# kitchen-timer.net
KiCad netlist of a schematic drawn in EAGLE
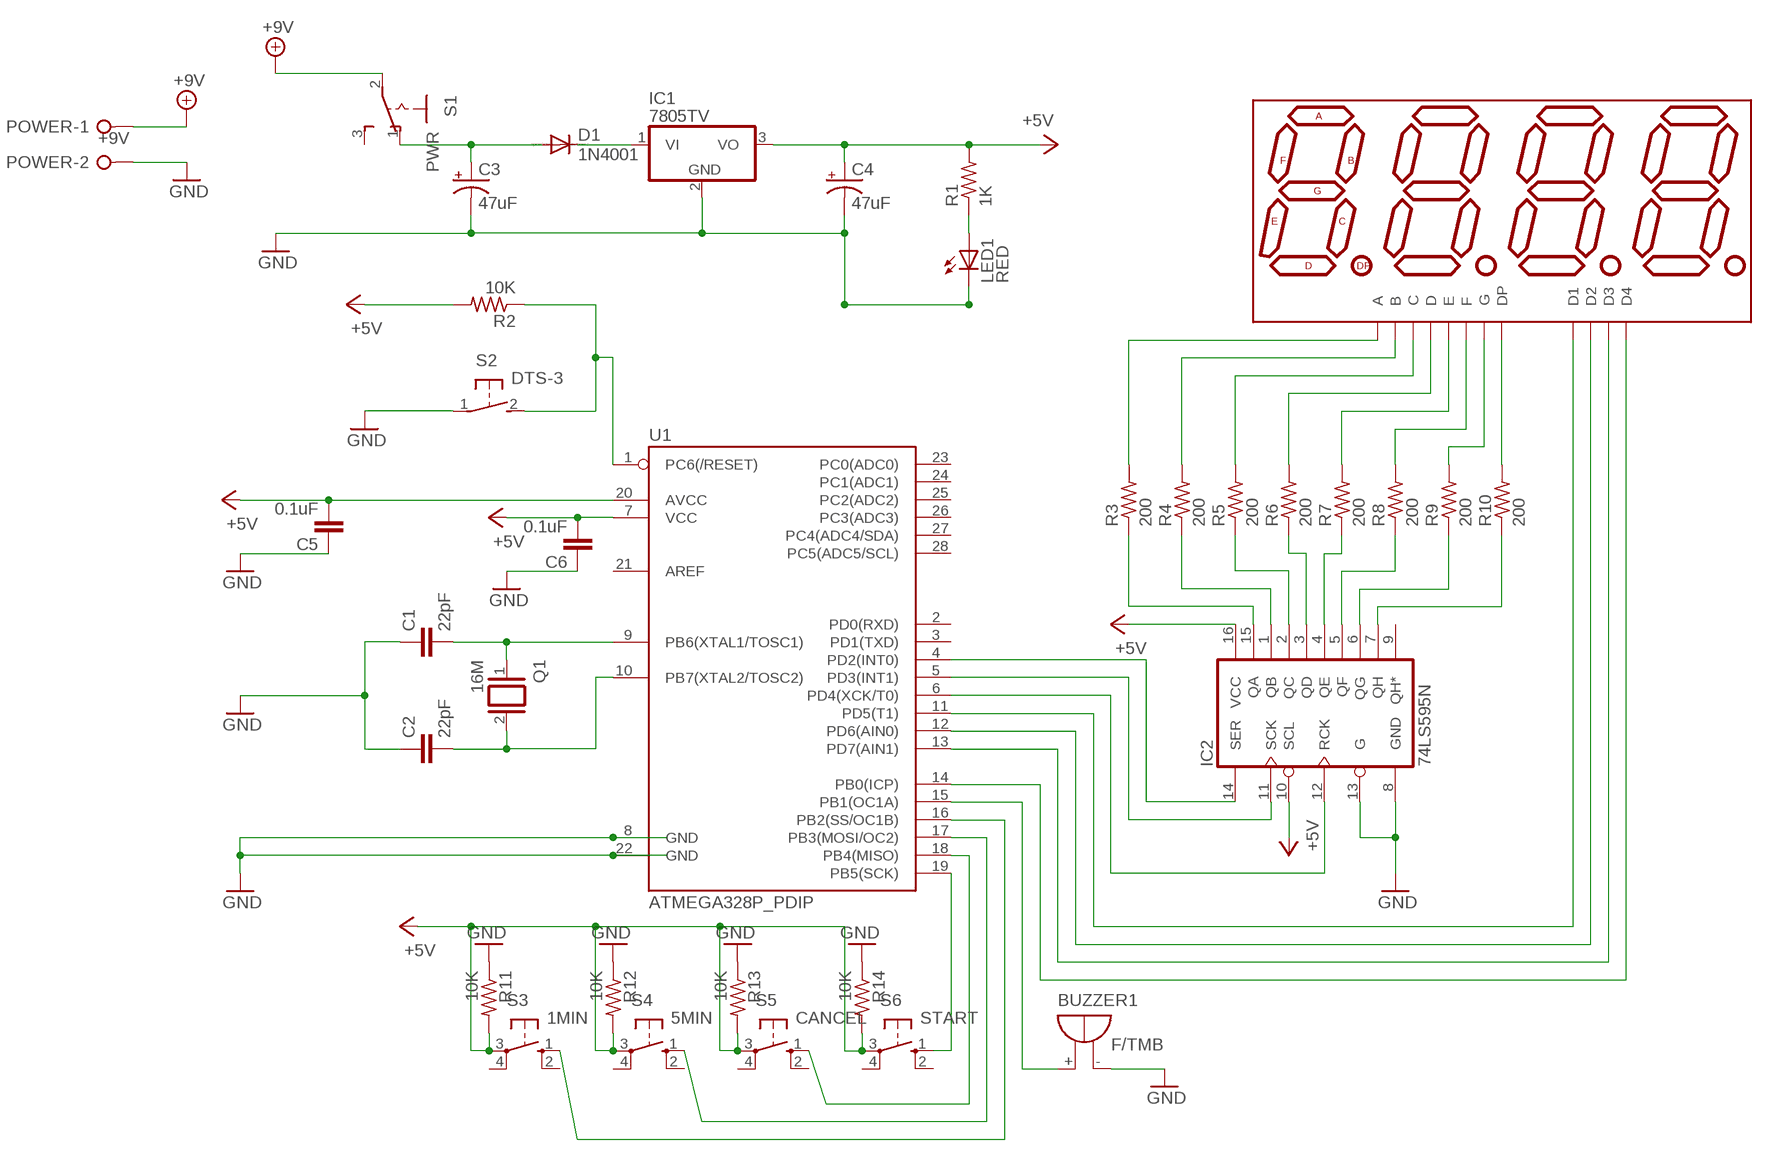
[diagram p0: schematic, sheet 1]

(export (version "E")
  (design (tool "Eeschema 10.0.6"))
  (components
    (comp (ref "BUZZER1")
      (value "F/TMB")
      (footprint "eagle-import:F_TMB")
      (libsource (lib "eagle-import") (part "F/TMB"))
    )
    (comp (ref "C1")
      (value "22pF")
      (footprint "eagle-import:C025-025X050")
      (libsource (lib "eagle-import") (part "C-EU025-025X050"))
    )
    (comp (ref "C2")
      (value "22pF")
      (footprint "eagle-import:C025-025X050")
      (libsource (lib "eagle-import") (part "C-EU025-025X050"))
    )
    (comp (ref "C3")
      (value "47uF")
      (footprint "eagle-import:E2,5-6E")
      (libsource (lib "eagle-import") (part "CPOL-USE2,5-6E"))
    )
    (comp (ref "C4")
      (value "47uF")
      (footprint "eagle-import:E2,5-6E")
      (libsource (lib "eagle-import") (part "CPOL-USE2,5-6E"))
    )
    (comp (ref "C5")
      (value "0.1uF")
      (footprint "eagle-import:C025-025X050")
      (libsource (lib "eagle-import") (part "C-EU025-025X050"))
    )
    (comp (ref "C6")
      (value "0.1uF")
      (footprint "eagle-import:C025-025X050")
      (libsource (lib "eagle-import") (part "C-EU025-025X050"))
    )
    (comp (ref "D1")
      (value "1N4001")
      (footprint "eagle-import:D-7.5")
      (libsource (lib "eagle-import") (part "DIODE-D-7.5"))
    )
    (comp (ref "DISP1")
      (value "7-SEGMENT-4DIGIT-COUNTER-HP-BUBBLE")
      (footprint "eagle-import:DIL12")
      (libsource (lib "eagle-import") (part "7-SEGMENT-4DIGIT-COUNTER-HP-BUBBLE"))
    )
    (comp (ref "IC1")
      (value "7805TV")
      (footprint "eagle-import:TO220V")
      (libsource (lib "eagle-import") (part "78TV05"))
    )
    (comp (ref "IC2")
      (value "74LS595N")
      (footprint "eagle-import:DIL16")
      (libsource (lib "eagle-import") (part "74595NLS"))
    )
    (comp (ref "LED1")
      (value "RED")
      (footprint "eagle-import:LED5MM")
      (libsource (lib "eagle-import") (part "LED5MM"))
    )
    (comp (ref "POWER")
      (value "+9V")
      (footprint "eagle-import:W237-132")
      (libsource (lib "eagle-import") (part "W237-02P"))
    )
    (comp (ref "Q1")
      (value "16M")
      (footprint "eagle-import:QS")
      (libsource (lib "eagle-import") (part "XTAL/S"))
    )
    (comp (ref "R1")
      (value "1K")
      (footprint "eagle-import:0204_7")
      (libsource (lib "eagle-import") (part "R-US_0204/7"))
    )
    (comp (ref "R2")
      (value "10K")
      (footprint "eagle-import:0204_7")
      (libsource (lib "eagle-import") (part "R-US_0204/7"))
    )
    (comp (ref "R3")
      (value "200")
      (footprint "eagle-import:0204_7")
      (libsource (lib "eagle-import") (part "R-US_0204/7"))
    )
    (comp (ref "R4")
      (value "200")
      (footprint "eagle-import:0204_7")
      (libsource (lib "eagle-import") (part "R-US_0204/7"))
    )
    (comp (ref "R5")
      (value "200")
      (footprint "eagle-import:0204_7")
      (libsource (lib "eagle-import") (part "R-US_0204/7"))
    )
    (comp (ref "R6")
      (value "200")
      (footprint "eagle-import:0204_7")
      (libsource (lib "eagle-import") (part "R-US_0204/7"))
    )
    (comp (ref "R7")
      (value "200")
      (footprint "eagle-import:0204_7")
      (libsource (lib "eagle-import") (part "R-US_0204/7"))
    )
    (comp (ref "R8")
      (value "200")
      (footprint "eagle-import:0204_7")
      (libsource (lib "eagle-import") (part "R-US_0204/7"))
    )
    (comp (ref "R9")
      (value "200")
      (footprint "eagle-import:0204_7")
      (libsource (lib "eagle-import") (part "R-US_0204/7"))
    )
    (comp (ref "R10")
      (value "200")
      (footprint "eagle-import:0204_7")
      (libsource (lib "eagle-import") (part "R-US_0204/7"))
    )
    (comp (ref "R11")
      (value "10K")
      (footprint "eagle-import:0204_7")
      (libsource (lib "eagle-import") (part "R-US_0204/7"))
    )
    (comp (ref "R12")
      (value "10K")
      (footprint "eagle-import:0204_7")
      (libsource (lib "eagle-import") (part "R-US_0204/7"))
    )
    (comp (ref "R13")
      (value "10K")
      (footprint "eagle-import:0204_7")
      (libsource (lib "eagle-import") (part "R-US_0204/7"))
    )
    (comp (ref "R14")
      (value "10K")
      (footprint "eagle-import:0204_7")
      (libsource (lib "eagle-import") (part "R-US_0204/7"))
    )
    (comp (ref "S1")
      (value "PWR")
      (footprint "eagle-import:255SB")
      (libsource (lib "eagle-import") (part "255SB"))
    )
    (comp (ref "S2")
      (value "DTS-3")
      (footprint "eagle-import:DTS-3")
      (libsource (lib "eagle-import") (part "DTS-3"))
    )
    (comp (ref "S3")
      (value "1MIN")
      (footprint "eagle-import:B3F-10XX")
      (fields (field (name "MPN") "B3F-1000"))
      (libsource (lib "eagle-import") (part "10-XX"))
    )
    (comp (ref "S4")
      (value "5MIN")
      (footprint "eagle-import:B3F-10XX")
      (fields (field (name "MPN") "B3F-1000"))
      (libsource (lib "eagle-import") (part "10-XX"))
    )
    (comp (ref "S5")
      (value "CANCEL")
      (footprint "eagle-import:B3F-10XX")
      (fields (field (name "MPN") "B3F-1000"))
      (libsource (lib "eagle-import") (part "10-XX"))
    )
    (comp (ref "S6")
      (value "START")
      (footprint "eagle-import:B3F-10XX")
      (fields (field (name "MPN") "B3F-1000"))
      (libsource (lib "eagle-import") (part "10-XX"))
    )
    (comp (ref "U1")
      (value "ATMEGA328P_PDIP")
      (footprint "eagle-import:DIL28-3")
      (libsource (lib "eagle-import") (part "ATMEGA328P_PDIP"))
    )
  )
  (nets
    (net (code "1") (name "+5V") (class "Default")
      (node (ref "C4") (pin "+") (pinfunction "+_+") (pintype "passive"))
      (node (ref "C5") (pin "2") (pinfunction "2_2") (pintype "passive"))
      (node (ref "C6") (pin "2") (pinfunction "2_2") (pintype "passive"))
      (node (ref "IC1") (pin "3") (pinfunction "VO_3") (pintype "passive"))
      (node (ref "IC2") (pin "10") (pinfunction "SCL_10") (pintype "input"))
      (node (ref "IC2") (pin "16") (pinfunction "VCC_16") (pintype "power_in"))
      (node (ref "R1") (pin "2") (pinfunction "2_2") (pintype "passive"))
      (node (ref "R11") (pin "2") (pinfunction "2_2") (pintype "passive"))
      (node (ref "R12") (pin "2") (pinfunction "2_2") (pintype "passive"))
      (node (ref "R13") (pin "2") (pinfunction "2_2") (pintype "passive"))
      (node (ref "R14") (pin "2") (pinfunction "2_2") (pintype "passive"))
      (node (ref "R2") (pin "2") (pinfunction "2_2") (pintype "passive"))
      (node (ref "S3") (pin "3") (pinfunction "P_3") (pintype "passive"))
      (node (ref "S4") (pin "3") (pinfunction "P_3") (pintype "passive"))
      (node (ref "S5") (pin "3") (pinfunction "P_3") (pintype "passive"))
      (node (ref "S6") (pin "3") (pinfunction "P_3") (pintype "passive"))
      (node (ref "U1") (pin "20") (pinfunction "AVCC_20") (pintype "bidirectional"))
      (node (ref "U1") (pin "7") (pinfunction "VCC_7") (pintype "bidirectional"))
    )
    (net (code "2") (name "+9V") (class "Default")
      (node (ref "POWER") (pin "1") (pinfunction "KL_1") (pintype "passive"))
      (node (ref "S1") (pin "2") (pinfunction "P_2") (pintype "passive"))
    )
    (net (code "3") (name "GND") (class "Default")
      (node (ref "BUZZER1") (pin "-") (pinfunction "-_-") (pintype "passive"))
      (node (ref "C1") (pin "1") (pinfunction "1_1") (pintype "passive"))
      (node (ref "C2") (pin "1") (pinfunction "1_1") (pintype "passive"))
      (node (ref "C3") (pin "-") (pinfunction "-_-") (pintype "passive"))
      (node (ref "C4") (pin "-") (pinfunction "-_-") (pintype "passive"))
      (node (ref "C5") (pin "1") (pinfunction "1_1") (pintype "passive"))
      (node (ref "C6") (pin "1") (pinfunction "1_1") (pintype "passive"))
      (node (ref "IC1") (pin "2") (pinfunction "GND_2") (pintype "passive"))
      (node (ref "IC2") (pin "13") (pinfunction "G_13") (pintype "input"))
      (node (ref "IC2") (pin "8") (pinfunction "GND_8") (pintype "power_in"))
      (node (ref "LED1") (pin "K") (pinfunction "C_K") (pintype "passive"))
      (node (ref "POWER") (pin "2") (pinfunction "KL_2") (pintype "passive"))
      (node (ref "R11") (pin "1") (pinfunction "1_1") (pintype "passive"))
      (node (ref "R12") (pin "1") (pinfunction "1_1") (pintype "passive"))
      (node (ref "R13") (pin "1") (pinfunction "1_1") (pintype "passive"))
      (node (ref "R14") (pin "1") (pinfunction "1_1") (pintype "passive"))
      (node (ref "S2") (pin "1") (pinfunction "1_1") (pintype "passive"))
      (node (ref "U1") (pin "22") (pinfunction "GND_22") (pintype "bidirectional"))
      (node (ref "U1") (pin "8") (pinfunction "GND_8") (pintype "bidirectional"))
    )
    (net (code "4") (name "Net-(DISP1-A)") (class "Default")
      (node (ref "DISP1") (pin "12") (pinfunction "A_12") (pintype "bidirectional"))
      (node (ref "R3") (pin "2") (pinfunction "2_2") (pintype "passive"))
    )
    (net (code "5") (name "Net-(DISP1-B)") (class "Default")
      (node (ref "DISP1") (pin "11") (pinfunction "B_11") (pintype "bidirectional"))
      (node (ref "R4") (pin "2") (pinfunction "2_2") (pintype "passive"))
    )
    (net (code "6") (name "Net-(DISP1-C)") (class "Default")
      (node (ref "DISP1") (pin "3") (pinfunction "C_3") (pintype "bidirectional"))
      (node (ref "R5") (pin "2") (pinfunction "2_2") (pintype "passive"))
    )
    (net (code "7") (name "Net-(DISP1-D)") (class "Default")
      (node (ref "DISP1") (pin "8") (pinfunction "D_8") (pintype "bidirectional"))
      (node (ref "R6") (pin "2") (pinfunction "2_2") (pintype "passive"))
    )
    (net (code "8") (name "Net-(DISP1-D1)") (class "Default")
      (node (ref "DISP1") (pin "1") (pinfunction "D1_1") (pintype "bidirectional"))
      (node (ref "U1") (pin "11") (pinfunction "PD5(T1)_11") (pintype "bidirectional"))
    )
    (net (code "9") (name "Net-(DISP1-D2)") (class "Default")
      (node (ref "DISP1") (pin "10") (pinfunction "D2_10") (pintype "bidirectional"))
      (node (ref "U1") (pin "12") (pinfunction "PD6(AIN0)_12") (pintype "bidirectional"))
    )
    (net (code "10") (name "Net-(DISP1-D3)") (class "Default")
      (node (ref "DISP1") (pin "4") (pinfunction "D3_4") (pintype "bidirectional"))
      (node (ref "U1") (pin "13") (pinfunction "PD7(AIN1)_13") (pintype "bidirectional"))
    )
    (net (code "11") (name "Net-(DISP1-D4)") (class "Default")
      (node (ref "DISP1") (pin "6") (pinfunction "D4_6") (pintype "bidirectional"))
      (node (ref "U1") (pin "14") (pinfunction "PB0(ICP)_14") (pintype "bidirectional"))
    )
    (net (code "12") (name "Net-(DISP1-DP)") (class "Default")
      (node (ref "DISP1") (pin "5") (pinfunction "DP_5") (pintype "bidirectional"))
      (node (ref "R10") (pin "2") (pinfunction "2_2") (pintype "passive"))
    )
    (net (code "13") (name "Net-(DISP1-E)") (class "Default")
      (node (ref "DISP1") (pin "2") (pinfunction "E_2") (pintype "bidirectional"))
      (node (ref "R7") (pin "2") (pinfunction "2_2") (pintype "passive"))
    )
    (net (code "14") (name "Net-(DISP1-F)") (class "Default")
      (node (ref "DISP1") (pin "9") (pinfunction "F_9") (pintype "bidirectional"))
      (node (ref "R8") (pin "2") (pinfunction "2_2") (pintype "passive"))
    )
    (net (code "15") (name "Net-(DISP1-G)") (class "Default")
      (node (ref "DISP1") (pin "7") (pinfunction "G_7") (pintype "bidirectional"))
      (node (ref "R9") (pin "2") (pinfunction "2_2") (pintype "passive"))
    )
    (net (code "16") (name "Net-(IC1-VI)") (class "Default")
      (node (ref "D1") (pin "C") (pinfunction "C_C") (pintype "passive"))
      (node (ref "IC1") (pin "1") (pinfunction "VI_1") (pintype "input"))
    )
    (net (code "17") (name "Net-(IC2-QA)") (class "Default")
      (node (ref "IC2") (pin "15") (pinfunction "QA_15") (pintype "tri_state"))
      (node (ref "R3") (pin "1") (pinfunction "1_1") (pintype "passive"))
    )
    (net (code "18") (name "Net-(IC2-QB)") (class "Default")
      (node (ref "IC2") (pin "1") (pinfunction "QB_1") (pintype "tri_state"))
      (node (ref "R4") (pin "1") (pinfunction "1_1") (pintype "passive"))
    )
    (net (code "19") (name "Net-(IC2-QC)") (class "Default")
      (node (ref "IC2") (pin "2") (pinfunction "QC_2") (pintype "tri_state"))
      (node (ref "R5") (pin "1") (pinfunction "1_1") (pintype "passive"))
    )
    (net (code "20") (name "Net-(IC2-QD)") (class "Default")
      (node (ref "IC2") (pin "3") (pinfunction "QD_3") (pintype "tri_state"))
      (node (ref "R6") (pin "1") (pinfunction "1_1") (pintype "passive"))
    )
    (net (code "21") (name "Net-(IC2-QE)") (class "Default")
      (node (ref "IC2") (pin "4") (pinfunction "QE_4") (pintype "tri_state"))
      (node (ref "R7") (pin "1") (pinfunction "1_1") (pintype "passive"))
    )
    (net (code "22") (name "Net-(IC2-QF)") (class "Default")
      (node (ref "IC2") (pin "5") (pinfunction "QF_5") (pintype "tri_state"))
      (node (ref "R8") (pin "1") (pinfunction "1_1") (pintype "passive"))
    )
    (net (code "23") (name "Net-(IC2-QG)") (class "Default")
      (node (ref "IC2") (pin "6") (pinfunction "QG_6") (pintype "tri_state"))
      (node (ref "R9") (pin "1") (pinfunction "1_1") (pintype "passive"))
    )
    (net (code "24") (name "Net-(IC2-QH)") (class "Default")
      (node (ref "IC2") (pin "7") (pinfunction "QH_7") (pintype "tri_state"))
      (node (ref "R10") (pin "1") (pinfunction "1_1") (pintype "passive"))
    )
    (net (code "25") (name "Net-(IC2-RCK)") (class "Default")
      (node (ref "IC2") (pin "12") (pinfunction "RCK_12") (pintype "input"))
      (node (ref "U1") (pin "6") (pinfunction "PD4(XCK/T0)_6") (pintype "bidirectional"))
    )
    (net (code "26") (name "Net-(IC2-SCK)") (class "Default")
      (node (ref "IC2") (pin "11") (pinfunction "SCK_11") (pintype "input"))
      (node (ref "U1") (pin "5") (pinfunction "PD3(INT1)_5") (pintype "bidirectional"))
    )
    (net (code "27") (name "Net-(IC2-SER)") (class "Default")
      (node (ref "IC2") (pin "14") (pinfunction "SER_14") (pintype "input"))
      (node (ref "U1") (pin "4") (pinfunction "PD2(INT0)_4") (pintype "bidirectional"))
    )
    (net (code "28") (name "Net-(LED1-PadA)") (class "Default")
      (node (ref "LED1") (pin "A") (pinfunction "A_A") (pintype "passive"))
      (node (ref "R1") (pin "1") (pinfunction "1_1") (pintype "passive"))
    )
    (net (code "29") (name "Net-(S1-O)") (class "Default")
      (node (ref "C3") (pin "+") (pinfunction "+_+") (pintype "passive"))
      (node (ref "D1") (pin "A") (pinfunction "A_A") (pintype "passive"))
      (node (ref "S1") (pin "1") (pinfunction "O_1") (pintype "passive"))
    )
    (net (code "30") (name "Net-(S3-S)") (class "Default")
      (node (ref "S3") (pin "1") (pinfunction "S_1") (pintype "passive"))
      (node (ref "U1") (pin "16") (pinfunction "PB2(SS/OC1B)_16") (pintype "bidirectional"))
    )
    (net (code "31") (name "Net-(S4-S)") (class "Default")
      (node (ref "S4") (pin "1") (pinfunction "S_1") (pintype "passive"))
      (node (ref "U1") (pin "17") (pinfunction "PB3(MOSI/OC2)_17") (pintype "bidirectional"))
    )
    (net (code "32") (name "Net-(S5-S)") (class "Default")
      (node (ref "S5") (pin "1") (pinfunction "S_1") (pintype "passive"))
      (node (ref "U1") (pin "18") (pinfunction "PB4(MISO)_18") (pintype "bidirectional"))
    )
    (net (code "33") (name "Net-(S6-S)") (class "Default")
      (node (ref "S6") (pin "1") (pinfunction "S_1") (pintype "passive"))
      (node (ref "U1") (pin "19") (pinfunction "PB5(SCK)_19") (pintype "bidirectional"))
    )
    (net (code "34") (name "Net-(U1-PB1(OC1A))") (class "Default")
      (node (ref "BUZZER1") (pin "+") (pinfunction "+_+") (pintype "passive"))
      (node (ref "U1") (pin "15") (pinfunction "PB1(OC1A)_15") (pintype "bidirectional"))
    )
    (net (code "35") (name "Net-(U1-PB6(XTAL1{slash}TOSC1))") (class "Default")
      (node (ref "C1") (pin "2") (pinfunction "2_2") (pintype "passive"))
      (node (ref "Q1") (pin "1") (pinfunction "1_1") (pintype "passive"))
      (node (ref "U1") (pin "9") (pinfunction "PB6(XTAL1/TOSC1)_9") (pintype "bidirectional"))
    )
    (net (code "36") (name "Net-(U1-PB7(XTAL2{slash}TOSC2))") (class "Default")
      (node (ref "C2") (pin "2") (pinfunction "2_2") (pintype "passive"))
      (node (ref "Q1") (pin "2") (pinfunction "2_2") (pintype "passive"))
      (node (ref "U1") (pin "10") (pinfunction "PB7(XTAL2/TOSC2)_10") (pintype "bidirectional"))
    )
    (net (code "37") (name "Net-(U1-PC6({slash}RESET))") (class "Default")
      (node (ref "R2") (pin "1") (pinfunction "1_1") (pintype "passive"))
      (node (ref "S2") (pin "2") (pinfunction "2_2") (pintype "passive"))
      (node (ref "U1") (pin "1") (pinfunction "PC6(/RESET)_1") (pintype "bidirectional"))
    )
    (net (code "38") (name "unconnected-(IC2-QH*-Pad9)") (class "Default")
      (node (ref "IC2") (pin "9") (pinfunction "QH*_9") (pintype "tri_state"))
    )
    (net (code "39") (name "unconnected-(S1-S-Pad3)") (class "Default")
      (node (ref "S1") (pin "3") (pinfunction "S_3") (pintype "passive"))
    )
    (net (code "40") (name "unconnected-(S3-P1-Pad4)") (class "Default")
      (node (ref "S3") (pin "4") (pinfunction "P1_4") (pintype "passive"))
    )
    (net (code "41") (name "unconnected-(S3-S1-Pad2)") (class "Default")
      (node (ref "S3") (pin "2") (pinfunction "S1_2") (pintype "passive"))
    )
    (net (code "42") (name "unconnected-(S4-P1-Pad4)") (class "Default")
      (node (ref "S4") (pin "4") (pinfunction "P1_4") (pintype "passive"))
    )
    (net (code "43") (name "unconnected-(S4-S1-Pad2)") (class "Default")
      (node (ref "S4") (pin "2") (pinfunction "S1_2") (pintype "passive"))
    )
    (net (code "44") (name "unconnected-(S5-P1-Pad4)") (class "Default")
      (node (ref "S5") (pin "4") (pinfunction "P1_4") (pintype "passive"))
    )
    (net (code "45") (name "unconnected-(S5-S1-Pad2)") (class "Default")
      (node (ref "S5") (pin "2") (pinfunction "S1_2") (pintype "passive"))
    )
    (net (code "46") (name "unconnected-(S6-P1-Pad4)") (class "Default")
      (node (ref "S6") (pin "4") (pinfunction "P1_4") (pintype "passive"))
    )
    (net (code "47") (name "unconnected-(S6-S1-Pad2)") (class "Default")
      (node (ref "S6") (pin "2") (pinfunction "S1_2") (pintype "passive"))
    )
    (net (code "48") (name "unconnected-(U1-AREF-Pad21)") (class "Default")
      (node (ref "U1") (pin "21") (pinfunction "AREF_21") (pintype "bidirectional"))
    )
    (net (code "49") (name "unconnected-(U1-PC0(ADC0)-Pad23)") (class "Default")
      (node (ref "U1") (pin "23") (pinfunction "PC0(ADC0)_23") (pintype "bidirectional"))
    )
    (net (code "50") (name "unconnected-(U1-PC1(ADC1)-Pad24)") (class "Default")
      (node (ref "U1") (pin "24") (pinfunction "PC1(ADC1)_24") (pintype "bidirectional"))
    )
    (net (code "51") (name "unconnected-(U1-PC2(ADC2)-Pad25)") (class "Default")
      (node (ref "U1") (pin "25") (pinfunction "PC2(ADC2)_25") (pintype "bidirectional"))
    )
    (net (code "52") (name "unconnected-(U1-PC3(ADC3)-Pad26)") (class "Default")
      (node (ref "U1") (pin "26") (pinfunction "PC3(ADC3)_26") (pintype "bidirectional"))
    )
    (net (code "53") (name "unconnected-(U1-PC4(ADC4{slash}SDA)-Pad27)") (class "Default")
      (node (ref "U1") (pin "27") (pinfunction "PC4(ADC4/SDA)_27") (pintype "bidirectional"))
    )
    (net (code "54") (name "unconnected-(U1-PC5(ADC5{slash}SCL)-Pad28)") (class "Default")
      (node (ref "U1") (pin "28") (pinfunction "PC5(ADC5/SCL)_28") (pintype "bidirectional"))
    )
    (net (code "55") (name "unconnected-(U1-PD0(RXD)-Pad2)") (class "Default")
      (node (ref "U1") (pin "2") (pinfunction "PD0(RXD)_2") (pintype "bidirectional"))
    )
    (net (code "56") (name "unconnected-(U1-PD1(TXD)-Pad3)") (class "Default")
      (node (ref "U1") (pin "3") (pinfunction "PD1(TXD)_3") (pintype "bidirectional"))
    )
  )
)
